# MOSFET.net
KiCad netlist of a schematic drawn in Altium Designer
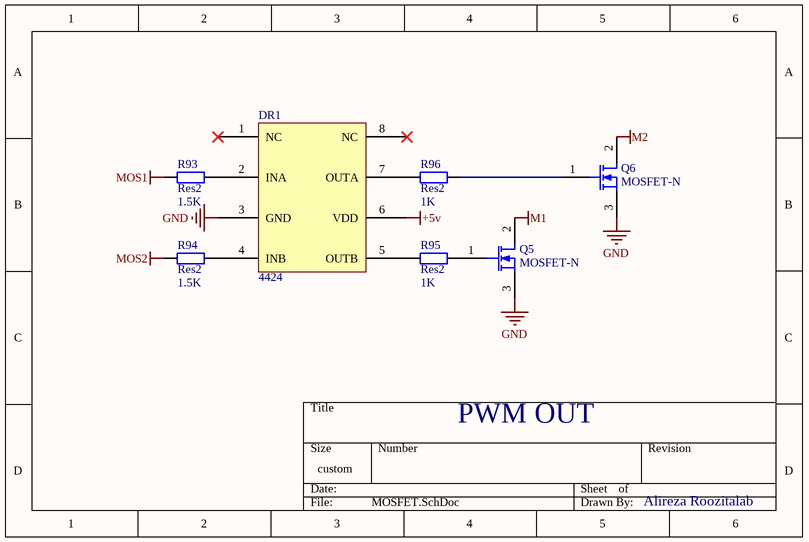
[diagram p0: MOSFET.SchDoc]

(export (version "E")
  (design (tool "Eeschema 10.0.6"))
  (components
    (comp (ref "DR1") (value "4424") (footprint "SOP8") (libsource (lib "my schem") (part "4424")))
    (comp (ref "Q5")
      (value "MOSFET-N")
      (footprint "dpak-to252")
      (description "N-Channel MOSFET")
      (fields (field (name "PUBLISHER") "Altium Limited"))
      (libsource (lib "Miscellaneous Devices") (part "MOSFET-N"))
    )
    (comp (ref "Q6")
      (value "MOSFET-N")
      (footprint "dpak-to252")
      (description "N-Channel MOSFET")
      (fields (field (name "PUBLISHER") "Altium Limited"))
      (libsource (lib "Miscellaneous Devices") (part "MOSFET-N"))
    )
    (comp (ref "R93")
      (value "Res2")
      (footprint "RES 1206 (3216X08L)")
      (description "Resistor")
      (fields (field (name "ALTIUM_VALUE") "1.5K") (field (name "PUBLISHER") "Altium Limited"))
      (libsource (lib "Miscellaneous Devices") (part "Res2"))
    )
    (comp (ref "R94")
      (value "Res2")
      (footprint "RES 1206 (3216X08L)")
      (description "Resistor")
      (fields (field (name "ALTIUM_VALUE") "1.5K") (field (name "PUBLISHER") "Altium Limited"))
      (libsource (lib "Miscellaneous Devices") (part "Res2"))
    )
    (comp (ref "R95")
      (value "Res2")
      (footprint "RES 1206 (3216X08L)")
      (description "Resistor")
      (fields (field (name "ALTIUM_VALUE") "1K") (field (name "PUBLISHER") "Altium Limited"))
      (libsource (lib "Miscellaneous Devices") (part "Res2"))
    )
    (comp (ref "R96")
      (value "Res2")
      (footprint "RES 1206 (3216X08L)")
      (description "Resistor")
      (fields (field (name "ALTIUM_VALUE") "1K") (field (name "PUBLISHER") "Altium Limited"))
      (libsource (lib "Miscellaneous Devices") (part "Res2"))
    )
  )
  (nets
    (net (code "1") (name "+5v") (class "Default")
      (node (ref "DR1") (pin "6") (pinfunction "VDD_6") (pintype "passive"))
    )
    (net (code "2") (name "GND") (class "Default")
      (node (ref "DR1") (pin "3") (pinfunction "GND_3") (pintype "passive"))
      (node (ref "Q5") (pin "3") (pinfunction "S_3") (pintype "passive"))
      (node (ref "Q6") (pin "3") (pinfunction "S_3") (pintype "passive"))
    )
    (net (code "3") (name "M1") (class "Default")
      (node (ref "Q5") (pin "2") (pinfunction "D_2") (pintype "passive"))
    )
    (net (code "4") (name "M2") (class "Default")
      (node (ref "Q6") (pin "2") (pinfunction "D_2") (pintype "passive"))
    )
    (net (code "5") (name "MOS1") (class "Default")
      (node (ref "R93") (pin "1") (pinfunction "1_1") (pintype "passive"))
    )
    (net (code "6") (name "MOS2") (class "Default")
      (node (ref "R94") (pin "1") (pinfunction "1_1") (pintype "passive"))
    )
    (net (code "7") (name "Net-(DR1-INA)") (class "Default")
      (node (ref "DR1") (pin "2") (pinfunction "INA_2") (pintype "passive"))
      (node (ref "R93") (pin "2") (pinfunction "2_2") (pintype "passive"))
    )
    (net (code "8") (name "Net-(DR1-INB)") (class "Default")
      (node (ref "DR1") (pin "4") (pinfunction "INB_4") (pintype "passive"))
      (node (ref "R94") (pin "2") (pinfunction "2_2") (pintype "passive"))
    )
    (net (code "9") (name "Net-(DR1-OUTA)") (class "Default")
      (node (ref "DR1") (pin "7") (pinfunction "OUTA_7") (pintype "passive"))
      (node (ref "R96") (pin "1") (pinfunction "1_1") (pintype "passive"))
    )
    (net (code "10") (name "Net-(DR1-OUTB)") (class "Default")
      (node (ref "DR1") (pin "5") (pinfunction "OUTB_5") (pintype "passive"))
      (node (ref "R95") (pin "1") (pinfunction "1_1") (pintype "passive"))
    )
    (net (code "11") (name "Net-(Q5-G)") (class "Default")
      (node (ref "Q5") (pin "1") (pinfunction "G_1") (pintype "passive"))
      (node (ref "R95") (pin "2") (pinfunction "2_2") (pintype "passive"))
    )
    (net (code "12") (name "Net-(Q6-G)") (class "Default")
      (node (ref "Q6") (pin "1") (pinfunction "G_1") (pintype "passive"))
      (node (ref "R96") (pin "2") (pinfunction "2_2") (pintype "passive"))
    )
    (net (code "13") (name "unconnected-(DR1-NC-Pad1)") (class "Default")
      (node (ref "DR1") (pin "1") (pinfunction "NC_1") (pintype "passive+no_connect"))
    )
    (net (code "14") (name "unconnected-(DR1-NC-Pad8)") (class "Default")
      (node (ref "DR1") (pin "8") (pinfunction "NC_8") (pintype "passive+no_connect"))
    )
  )
)
